# 13_IO_ETH.net
KiCad netlist of a schematic drawn in Altium Designer
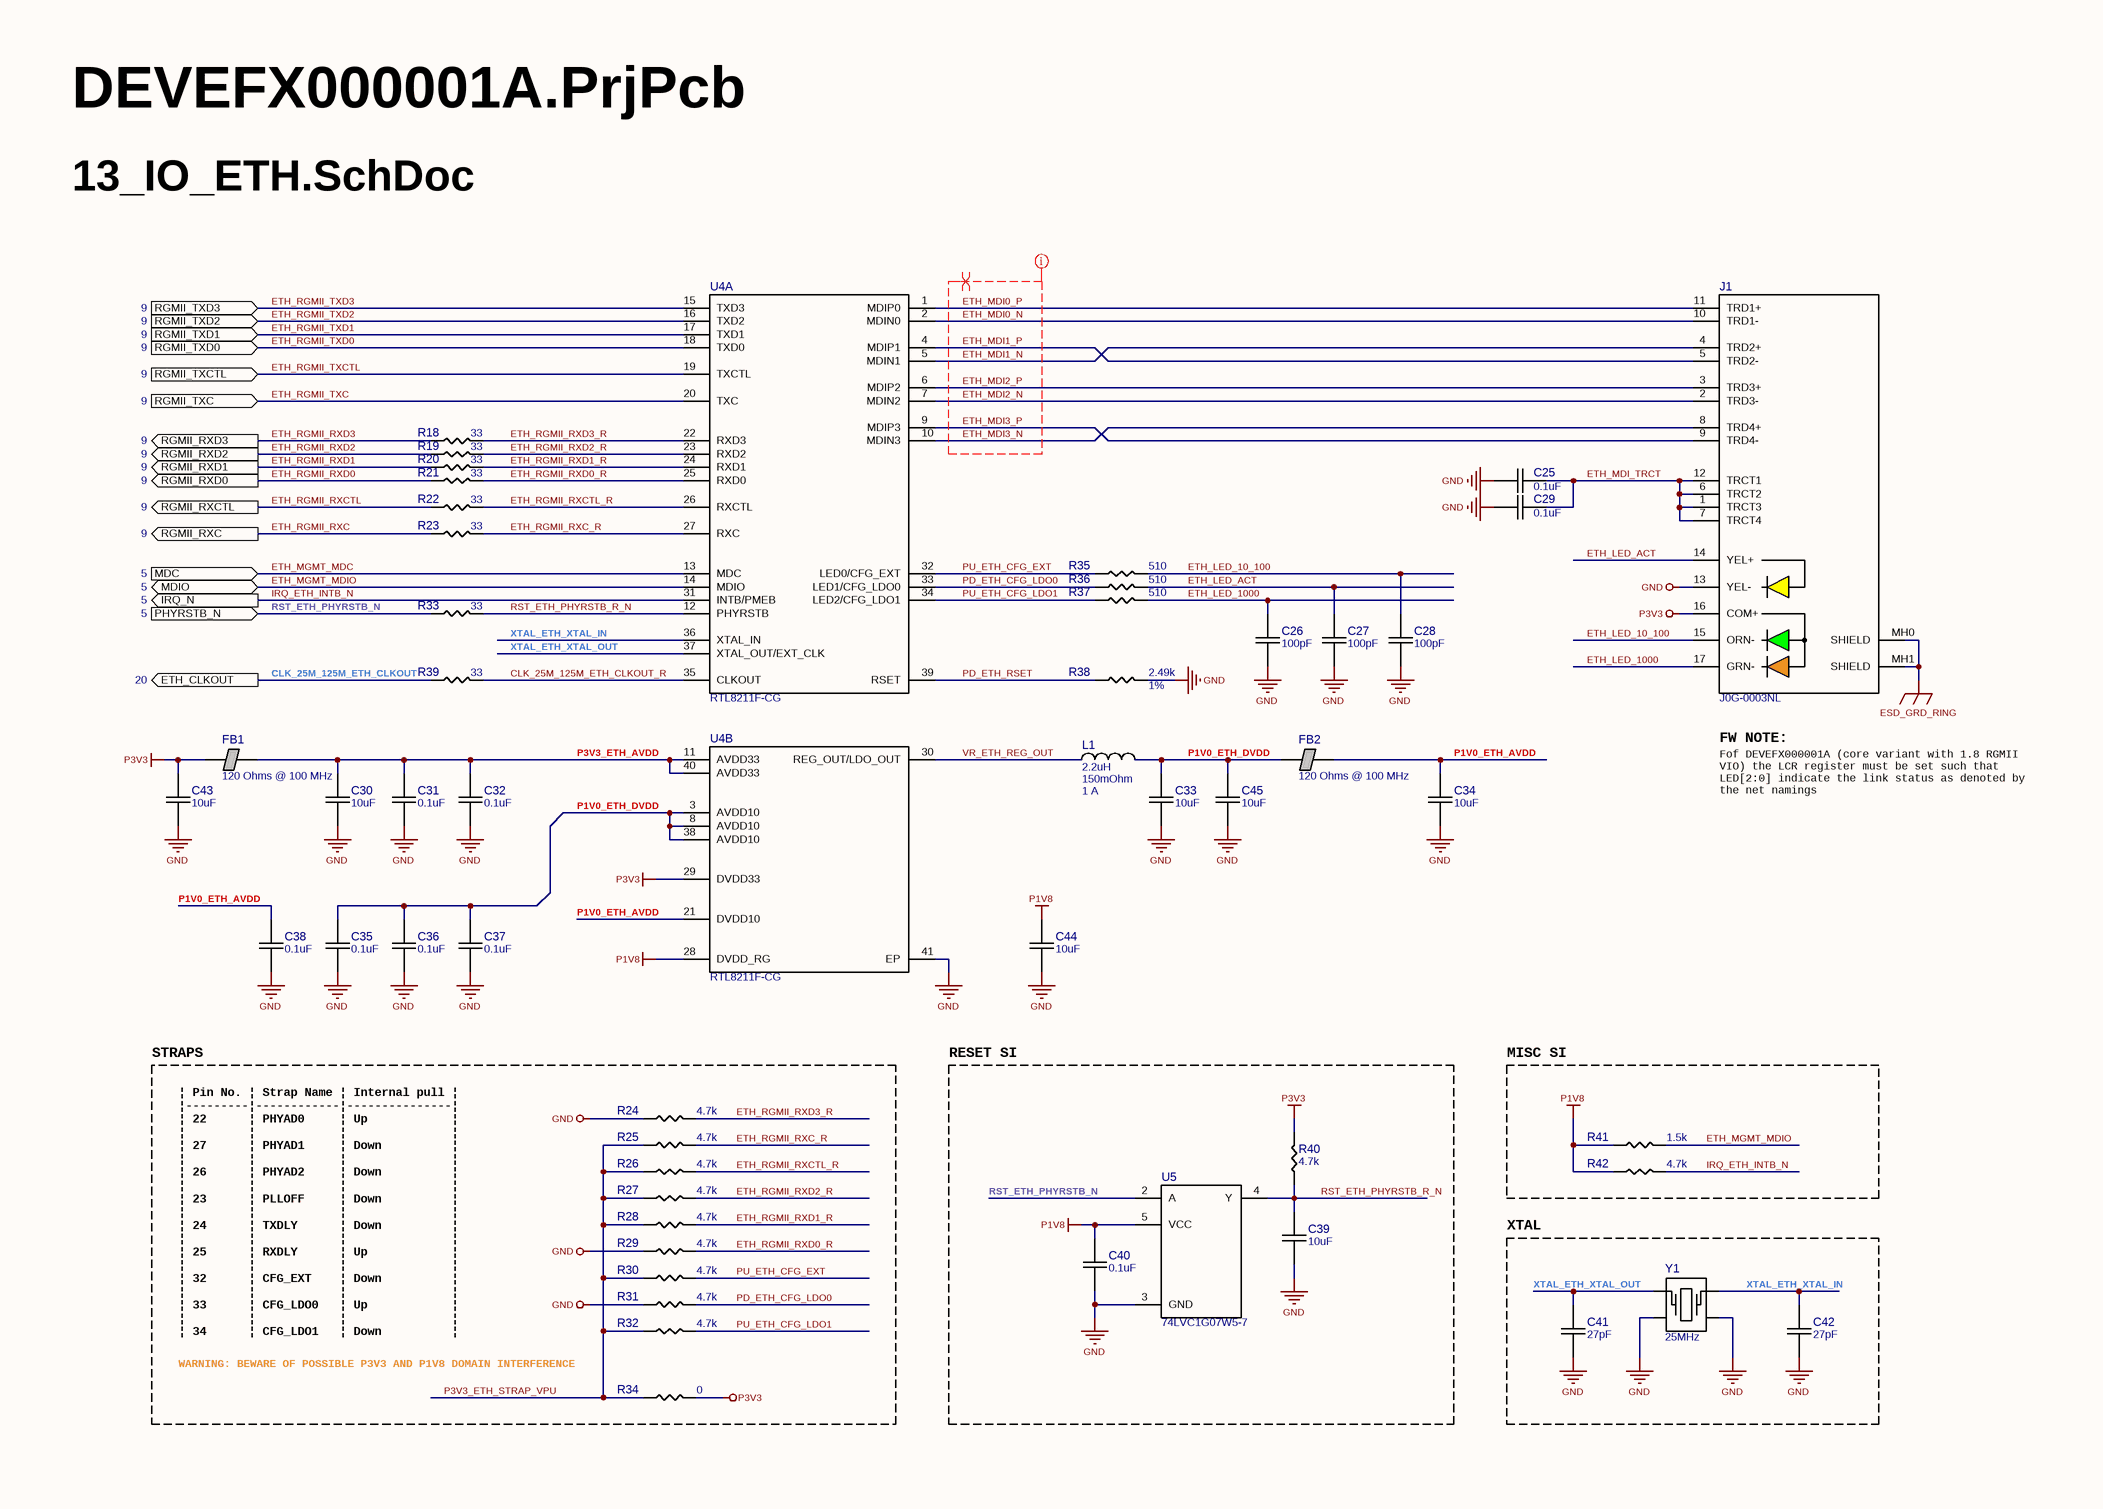
[diagram p0: 13_IO_ETH.SchDoc]

(export (version "E")
  (design (tool "Eeschema 10.0.6"))
  (components
    (comp (ref "C25")
      (value "0.1uF")
      (footprint "CAPC1005X06N")
      (description "CAP CER 0.1UF 25V X7R 0402")
      (fields (field (name "PART NUMBER") "GRM155R71E104KE14J") (field (name "VOLTAGE") "25V"))
      (libsource (lib "Database") (part "Capacitor"))
    )
    (comp (ref "C26")
      (value "100pF")
      (footprint "CAPC1005X06N")
      (description "CAP CER 100PF 50V C0G/NP0 0402")
      (fields (field (name "PART NUMBER") "GCM1555C1H101FA16J") (field (name "VOLTAGE") "50V"))
      (libsource (lib "Database") (part "Capacitor"))
    )
    (comp (ref "C27")
      (value "100pF")
      (footprint "CAPC1005X06N")
      (description "CAP CER 100PF 50V C0G/NP0 0402")
      (fields (field (name "PART NUMBER") "GCM1555C1H101FA16J") (field (name "VOLTAGE") "50V"))
      (libsource (lib "Database") (part "Capacitor"))
    )
    (comp (ref "C28")
      (value "100pF")
      (footprint "CAPC1005X06N")
      (description "CAP CER 100PF 50V C0G/NP0 0402")
      (fields (field (name "PART NUMBER") "GCM1555C1H101FA16J") (field (name "VOLTAGE") "50V"))
      (libsource (lib "Database") (part "Capacitor"))
    )
    (comp (ref "C29")
      (value "0.1uF")
      (footprint "CAPC1005X06N")
      (description "CAP CER 0.1UF 25V X7R 0402")
      (fields (field (name "PART NUMBER") "GRM155R71E104KE14J") (field (name "VOLTAGE") "25V"))
      (libsource (lib "Database") (part "Capacitor"))
    )
    (comp (ref "C30")
      (value "10uF")
      (footprint "CAPC1005X06N")
      (description "CAP CER 10UF 6.3V X5R 0402")
      (fields (field (name "PART NUMBER") "GRM155R60J106ME47D") (field (name "VOLTAGE") "6.3V"))
      (libsource (lib "Database") (part "Capacitor"))
    )
    (comp (ref "C31")
      (value "0.1uF")
      (footprint "CAPC1005X06N")
      (description "CAP CER 0.1UF 25V X7R 0402")
      (fields (field (name "PART NUMBER") "GRM155R71E104KE14J") (field (name "VOLTAGE") "25V"))
      (libsource (lib "Database") (part "Capacitor"))
    )
    (comp (ref "C32")
      (value "0.1uF")
      (footprint "CAPC1005X06N")
      (description "CAP CER 0.1UF 25V X7R 0402")
      (fields (field (name "PART NUMBER") "GRM155R71E104KE14J") (field (name "VOLTAGE") "25V"))
      (libsource (lib "Database") (part "Capacitor"))
    )
    (comp (ref "C33")
      (value "10uF")
      (footprint "CAPC1005X06N")
      (description "CAP CER 10UF 6.3V X5R 0402")
      (fields (field (name "PART NUMBER") "GRM155R60J106ME47D") (field (name "VOLTAGE") "6.3V"))
      (libsource (lib "Database") (part "Capacitor"))
    )
    (comp (ref "C34")
      (value "10uF")
      (footprint "CAPC1005X06N")
      (description "CAP CER 10UF 6.3V X5R 0402")
      (fields (field (name "PART NUMBER") "GRM155R60J106ME47D") (field (name "VOLTAGE") "6.3V"))
      (libsource (lib "Database") (part "Capacitor"))
    )
    (comp (ref "C35")
      (value "0.1uF")
      (footprint "CAPC1005X06N")
      (description "CAP CER 0.1UF 25V X7R 0402")
      (fields (field (name "PART NUMBER") "GRM155R71E104KE14J") (field (name "VOLTAGE") "25V"))
      (libsource (lib "Database") (part "Capacitor"))
    )
    (comp (ref "C36")
      (value "0.1uF")
      (footprint "CAPC1005X06N")
      (description "CAP CER 0.1UF 25V X7R 0402")
      (fields (field (name "PART NUMBER") "GRM155R71E104KE14J") (field (name "VOLTAGE") "25V"))
      (libsource (lib "Database") (part "Capacitor"))
    )
    (comp (ref "C37")
      (value "0.1uF")
      (footprint "CAPC1005X06N")
      (description "CAP CER 0.1UF 25V X7R 0402")
      (fields (field (name "PART NUMBER") "GRM155R71E104KE14J") (field (name "VOLTAGE") "25V"))
      (libsource (lib "Database") (part "Capacitor"))
    )
    (comp (ref "C38")
      (value "0.1uF")
      (footprint "CAPC1005X06N")
      (description "CAP CER 0.1UF 25V X7R 0402")
      (fields (field (name "PART NUMBER") "GRM155R71E104KE14J") (field (name "VOLTAGE") "25V"))
      (libsource (lib "Database") (part "Capacitor"))
    )
    (comp (ref "C39")
      (value "10uF")
      (footprint "CAPC1005X06N")
      (description "CAP CER 10UF 6.3V X5R 0402")
      (fields (field (name "PART NUMBER") "GRM155R60J106ME47D") (field (name "VOLTAGE") "6.3V"))
      (libsource (lib "Database") (part "Capacitor"))
    )
    (comp (ref "C40")
      (value "0.1uF")
      (footprint "CAPC1005X06N")
      (description "CAP CER 0.1UF 25V X7R 0402")
      (fields (field (name "PART NUMBER") "GRM155R71E104KE14J") (field (name "VOLTAGE") "25V"))
      (libsource (lib "Database") (part "Capacitor"))
    )
    (comp (ref "C41")
      (value "27pF")
      (footprint "CAPC1005X06N")
      (description "CAP CER 27PF 50V C0G/NPO 0402")
      (fields (field (name "PART NUMBER") "CC0402JRNPO9BN270") (field (name "VOLTAGE") "50V"))
      (libsource (lib "Database") (part "Capacitor"))
    )
    (comp (ref "C42")
      (value "27pF")
      (footprint "CAPC1005X06N")
      (description "CAP CER 27PF 50V C0G/NPO 0402")
      (fields (field (name "PART NUMBER") "CC0402JRNPO9BN270") (field (name "VOLTAGE") "50V"))
      (libsource (lib "Database") (part "Capacitor"))
    )
    (comp (ref "C43")
      (value "10uF")
      (footprint "CAPC1005X06N")
      (description "CAP CER 10UF 6.3V X5R 0402")
      (fields (field (name "PART NUMBER") "GRM155R60J106ME47D") (field (name "VOLTAGE") "6.3V"))
      (libsource (lib "Database") (part "Capacitor"))
    )
    (comp (ref "C44")
      (value "10uF")
      (footprint "CAPC1005X06N")
      (description "CAP CER 10UF 6.3V X5R 0402")
      (fields (field (name "PART NUMBER") "GRM155R60J106ME47D") (field (name "VOLTAGE") "6.3V"))
      (libsource (lib "Database") (part "Capacitor"))
    )
    (comp (ref "C45")
      (value "10uF")
      (footprint "CAPC1005X06N")
      (description "CAP CER 10UF 6.3V X5R 0402")
      (fields (field (name "PART NUMBER") "GRM155R60J106ME47D") (field (name "VOLTAGE") "6.3V"))
      (libsource (lib "Database") (part "Capacitor"))
    )
    (comp (ref "FB1")
      (value "120 Ohms @ 100 MHz")
      (footprint "INDC1005X05N")
      (description "FERRITE BEAD 120 OHM 0402 1LN")
      (fields (field (name "PART NUMBER") "BLM15PD121SN1D"))
      (libsource (lib "Database") (part "Bead"))
    )
    (comp (ref "FB2")
      (value "120 Ohms @ 100 MHz")
      (footprint "INDC1005X05N")
      (description "FERRITE BEAD 120 OHM 0402 1LN")
      (fields (field (name "PART NUMBER") "BLM15PD121SN1D"))
      (libsource (lib "Database") (part "Bead"))
    )
    (comp (ref "J1")
      (value "J0G-0003NL")
      (footprint "PULSE_J0G-0003NL")
      (description "CONN JACK 1PORT 1000 BASE-T PCB")
      (libsource (lib "Database") (part "J0G-0003NL"))
    )
    (comp (ref "L1")
      (value "2.2uH")
      (footprint "INDC2520X12N")
      (description "FIXED IND 2.2UH 1A 150 MOHM SMD")
      (fields
        (field (name "PART NUMBER") "LQM2HPN2R2MJ0L")
        (field (name "DCR") "150mOhm")
        (field (name "IR") "1 A")
      )
      (libsource (lib "Database") (part "Inductor"))
    )
    (comp (ref "R18")
      (value "33")
      (footprint "RESC1005X03N")
      (description "RES SMD 33 OHM 1% 1/16W 0402")
      (fields (field (name "PART NUMBER") "RC0402FR-0733RL"))
      (libsource (lib "Database") (part "Resistor_ENG"))
    )
    (comp (ref "R19")
      (value "33")
      (footprint "RESC1005X03N")
      (description "RES SMD 33 OHM 1% 1/16W 0402")
      (fields (field (name "PART NUMBER") "RC0402FR-0733RL"))
      (libsource (lib "Database") (part "Resistor_ENG"))
    )
    (comp (ref "R20")
      (value "33")
      (footprint "RESC1005X03N")
      (description "RES SMD 33 OHM 1% 1/16W 0402")
      (fields (field (name "PART NUMBER") "RC0402FR-0733RL"))
      (libsource (lib "Database") (part "Resistor_ENG"))
    )
    (comp (ref "R21")
      (value "33")
      (footprint "RESC1005X03N")
      (description "RES SMD 33 OHM 1% 1/16W 0402")
      (fields (field (name "PART NUMBER") "RC0402FR-0733RL"))
      (libsource (lib "Database") (part "Resistor_ENG"))
    )
    (comp (ref "R22")
      (value "33")
      (footprint "RESC1005X03N")
      (description "RES SMD 33 OHM 1% 1/16W 0402")
      (fields (field (name "PART NUMBER") "RC0402FR-0733RL"))
      (libsource (lib "Database") (part "Resistor_ENG"))
    )
    (comp (ref "R23")
      (value "33")
      (footprint "RESC1005X03N")
      (description "RES SMD 33 OHM 1% 1/16W 0402")
      (fields (field (name "PART NUMBER") "RC0402FR-0733RL"))
      (libsource (lib "Database") (part "Resistor_ENG"))
    )
    (comp (ref "R24")
      (value "4.7k")
      (footprint "RESC1005X03N")
      (description "RES SMD 4.7K OHM 1% 1/16W 0402")
      (fields (field (name "PART NUMBER") "RC0402FR-074K7L"))
      (libsource (lib "Database") (part "Resistor_ENG"))
    )
    (comp (ref "R25")
      (value "4.7k")
      (footprint "RESC1005X03N")
      (description "RES SMD 4.7K OHM 1% 1/16W 0402")
      (fields (field (name "PART NUMBER") "RC0402FR-074K7L"))
      (libsource (lib "Database") (part "Resistor_ENG"))
    )
    (comp (ref "R26")
      (value "4.7k")
      (footprint "RESC1005X03N")
      (description "RES SMD 4.7K OHM 1% 1/16W 0402")
      (fields (field (name "PART NUMBER") "RC0402FR-074K7L"))
      (libsource (lib "Database") (part "Resistor_ENG"))
    )
    (comp (ref "R27")
      (value "4.7k")
      (footprint "RESC1005X03N")
      (description "RES SMD 4.7K OHM 1% 1/16W 0402")
      (fields (field (name "PART NUMBER") "RC0402FR-074K7L"))
      (libsource (lib "Database") (part "Resistor_ENG"))
    )
    (comp (ref "R28")
      (value "4.7k")
      (footprint "RESC1005X03N")
      (description "RES SMD 4.7K OHM 1% 1/16W 0402")
      (fields (field (name "PART NUMBER") "RC0402FR-074K7L"))
      (libsource (lib "Database") (part "Resistor_ENG"))
    )
    (comp (ref "R29")
      (value "4.7k")
      (footprint "RESC1005X03N")
      (description "RES SMD 4.7K OHM 1% 1/16W 0402")
      (fields (field (name "PART NUMBER") "RC0402FR-074K7L"))
      (libsource (lib "Database") (part "Resistor_ENG"))
    )
    (comp (ref "R30")
      (value "4.7k")
      (footprint "RESC1005X03N")
      (description "RES SMD 4.7K OHM 1% 1/16W 0402")
      (fields (field (name "PART NUMBER") "RC0402FR-074K7L"))
      (libsource (lib "Database") (part "Resistor_ENG"))
    )
    (comp (ref "R31")
      (value "4.7k")
      (footprint "RESC1005X03N")
      (description "RES SMD 4.7K OHM 1% 1/16W 0402")
      (fields (field (name "PART NUMBER") "RC0402FR-074K7L"))
      (libsource (lib "Database") (part "Resistor_ENG"))
    )
    (comp (ref "R32")
      (value "4.7k")
      (footprint "RESC1005X03N")
      (description "RES SMD 4.7K OHM 1% 1/16W 0402")
      (fields (field (name "PART NUMBER") "RC0402FR-074K7L"))
      (libsource (lib "Database") (part "Resistor_ENG"))
    )
    (comp (ref "R33")
      (value "33")
      (footprint "RESC1005X03N")
      (description "RES SMD 33 OHM 1% 1/16W 0402")
      (fields (field (name "PART NUMBER") "RC0402FR-0733RL"))
      (libsource (lib "Database") (part "Resistor_ENG"))
    )
    (comp (ref "R34")
      (value "0")
      (footprint "RESC1005X03N")
      (description "RES SMD 0 OHM JUMPER 1/16W 0402")
      (fields (field (name "PART NUMBER") "RC0402FR-070RL"))
      (libsource (lib "Database") (part "Resistor_ENG"))
    )
    (comp (ref "R35")
      (value "510")
      (footprint "RESC1005X03N")
      (description "RES 510 OHM 5% 1/16W 0402")
      (fields (field (name "PART NUMBER") "RC0402JR-07510RL"))
      (libsource (lib "Database") (part "Resistor_ENG"))
    )
    (comp (ref "R36")
      (value "510")
      (footprint "RESC1005X03N")
      (description "RES 510 OHM 5% 1/16W 0402")
      (fields (field (name "PART NUMBER") "RC0402JR-07510RL"))
      (libsource (lib "Database") (part "Resistor_ENG"))
    )
    (comp (ref "R37")
      (value "510")
      (footprint "RESC1005X03N")
      (description "RES 510 OHM 5% 1/16W 0402")
      (fields (field (name "PART NUMBER") "RC0402JR-07510RL"))
      (libsource (lib "Database") (part "Resistor_ENG"))
    )
    (comp (ref "R38")
      (value "2.49k")
      (footprint "RESC1005X03N")
      (description "RES SMD 2.49K OHM 1% 1/16W 0402")
      (fields (field (name "PART NUMBER") "RC0402FR-072K49L") (field (name "TOL") "1%"))
      (libsource (lib "Database") (part "Resistor_ENG"))
    )
    (comp (ref "R39")
      (value "33")
      (footprint "RESC1005X03N")
      (description "RES SMD 33 OHM 1% 1/16W 0402")
      (fields (field (name "PART NUMBER") "RC0402FR-0733RL"))
      (libsource (lib "Database") (part "Resistor_ENG"))
    )
    (comp (ref "R40")
      (value "4.7k")
      (footprint "RESC1005X03N")
      (description "RES SMD 4.7K OHM 1% 1/16W 0402")
      (fields (field (name "PART NUMBER") "RC0402FR-074K7L"))
      (libsource (lib "Database") (part "Resistor_ENG"))
    )
    (comp (ref "R41")
      (value "1.5k")
      (footprint "RESC1005X03N")
      (description "RES 1.5K OHM 1% 1/16W 0402")
      (fields (field (name "PART NUMBER") "RC0402FR-071K5L"))
      (libsource (lib "Database") (part "Resistor_ENG"))
    )
    (comp (ref "R42")
      (value "4.7k")
      (footprint "RESC1005X03N")
      (description "RES SMD 4.7K OHM 1% 1/16W 0402")
      (fields (field (name "PART NUMBER") "RC0402FR-074K7L"))
      (libsource (lib "Database") (part "Resistor_ENG"))
    )
    (comp (ref "U4")
      (value "RTL8211F-CG")
      (footprint "QFN40P500X500X90_HS-41N")
      (description "Phy 1-CH 10MBPS/100MBPS/1GBPS 3.3V 40-PIN QFN Ep")
      (libsource (lib "Database") (part "RTL8211F"))
    )
    (comp (ref "U5")
      (value "74LVC1G07W5-7")
      (footprint "SOT95P280X145-5N")
      (description "IC BUFFER NON-INVERT 5.5V SOT25")
      (libsource (lib "Database") (part "74LVC1G07_SOT"))
    )
    (comp (ref "Y1")
      (value "25MHz")
      (footprint "XTAL_3225")
      (description "CRYSTAL 25.0000MHZ 18PF SMD")
      (fields (field (name "PART NUMBER") "TSX-3225 25.0000MF10P-C0"))
      (libsource (lib "Database") (part "Crystal_1"))
    )
  )
  (nets
    (net (code "1") (name "/CLK_25M_125M_ETH_CLKOUT") (class "Default")
      (node (ref "R39") (pin "1") (pinfunction "1_1") (pintype "passive"))
    )
    (net (code "2") (name "/CLK_25M_125M_ETH_CLKOUT_R") (class "Default")
      (node (ref "R39") (pin "2") (pinfunction "2_2") (pintype "passive"))
      (node (ref "U4") (pin "35") (pinfunction "CLKOUT_35") (pintype "passive"))
    )
    (net (code "3") (name "/ETH_LED_10_100") (class "Default")
      (node (ref "C28") (pin "2") (pinfunction "2_2") (pintype "passive"))
      (node (ref "J1") (pin "15") (pinfunction "ORN-_15") (pintype "passive"))
      (node (ref "R35") (pin "2") (pinfunction "2_2") (pintype "passive"))
    )
    (net (code "4") (name "/ETH_LED_1000") (class "Default")
      (node (ref "C26") (pin "2") (pinfunction "2_2") (pintype "passive"))
      (node (ref "J1") (pin "17") (pinfunction "GRN-_17") (pintype "passive"))
      (node (ref "R37") (pin "2") (pinfunction "2_2") (pintype "passive"))
    )
    (net (code "5") (name "/ETH_LED_ACT") (class "Default")
      (node (ref "C27") (pin "2") (pinfunction "2_2") (pintype "passive"))
      (node (ref "J1") (pin "14") (pinfunction "YEL+_14") (pintype "passive"))
      (node (ref "R36") (pin "2") (pinfunction "2_2") (pintype "passive"))
    )
    (net (code "6") (name "/ETH_MDI0_N") (class "Default")
      (node (ref "J1") (pin "10") (pinfunction "TRD1-_10") (pintype "passive"))
      (node (ref "U4") (pin "2") (pinfunction "MDIN0_2") (pintype "passive"))
    )
    (net (code "7") (name "/ETH_MDI0_P") (class "Default")
      (node (ref "J1") (pin "11") (pinfunction "TRD1+_11") (pintype "passive"))
      (node (ref "U4") (pin "1") (pinfunction "MDIP0_1") (pintype "passive"))
    )
    (net (code "8") (name "/ETH_MDI1_N") (class "Default")
      (node (ref "J1") (pin "4") (pinfunction "TRD2+_4") (pintype "passive"))
      (node (ref "U4") (pin "5") (pinfunction "MDIN1_5") (pintype "passive"))
    )
    (net (code "9") (name "/ETH_MDI1_P") (class "Default")
      (node (ref "J1") (pin "5") (pinfunction "TRD2-_5") (pintype "passive"))
      (node (ref "U4") (pin "4") (pinfunction "MDIP1_4") (pintype "passive"))
    )
    (net (code "10") (name "/ETH_MDI2_N") (class "Default")
      (node (ref "J1") (pin "2") (pinfunction "TRD3-_2") (pintype "passive"))
      (node (ref "U4") (pin "7") (pinfunction "MDIN2_7") (pintype "passive"))
    )
    (net (code "11") (name "/ETH_MDI2_P") (class "Default")
      (node (ref "J1") (pin "3") (pinfunction "TRD3+_3") (pintype "passive"))
      (node (ref "U4") (pin "6") (pinfunction "MDIP2_6") (pintype "passive"))
    )
    (net (code "12") (name "/ETH_MDI3_N") (class "Default")
      (node (ref "J1") (pin "8") (pinfunction "TRD4+_8") (pintype "passive"))
      (node (ref "U4") (pin "10") (pinfunction "MDIN3_10") (pintype "passive"))
    )
    (net (code "13") (name "/ETH_MDI3_P") (class "Default")
      (node (ref "J1") (pin "9") (pinfunction "TRD4-_9") (pintype "passive"))
      (node (ref "U4") (pin "9") (pinfunction "MDIP3_9") (pintype "passive"))
    )
    (net (code "14") (name "/ETH_MDI_TRCT") (class "Default")
      (node (ref "C25") (pin "2") (pinfunction "2_2") (pintype "passive"))
      (node (ref "C29") (pin "2") (pinfunction "2_2") (pintype "passive"))
      (node (ref "J1") (pin "1") (pinfunction "TRCT3_1") (pintype "passive"))
      (node (ref "J1") (pin "12") (pinfunction "TRCT1_12") (pintype "passive"))
      (node (ref "J1") (pin "6") (pinfunction "TRCT2_6") (pintype "passive"))
      (node (ref "J1") (pin "7") (pinfunction "TRCT4_7") (pintype "passive"))
    )
    (net (code "15") (name "/ETH_MGMT_MDC") (class "Default")
      (node (ref "U4") (pin "13") (pinfunction "MDC_13") (pintype "passive"))
    )
    (net (code "16") (name "/ETH_MGMT_MDIO") (class "Default")
      (node (ref "R41") (pin "2") (pinfunction "2_2") (pintype "passive"))
      (node (ref "U4") (pin "14") (pinfunction "MDIO_14") (pintype "passive"))
    )
    (net (code "17") (name "/ETH_RGMII_RXC") (class "Default")
      (node (ref "R23") (pin "1") (pinfunction "1_1") (pintype "passive"))
    )
    (net (code "18") (name "/ETH_RGMII_RXCTL") (class "Default")
      (node (ref "R22") (pin "1") (pinfunction "1_1") (pintype "passive"))
    )
    (net (code "19") (name "/ETH_RGMII_RXCTL_R") (class "Default")
      (node (ref "R22") (pin "2") (pinfunction "2_2") (pintype "passive"))
      (node (ref "R26") (pin "2") (pinfunction "2_2") (pintype "passive"))
      (node (ref "U4") (pin "26") (pinfunction "RXCTL_26") (pintype "passive"))
    )
    (net (code "20") (name "/ETH_RGMII_RXC_R") (class "Default")
      (node (ref "R23") (pin "2") (pinfunction "2_2") (pintype "passive"))
      (node (ref "R25") (pin "2") (pinfunction "2_2") (pintype "passive"))
      (node (ref "U4") (pin "27") (pinfunction "RXC_27") (pintype "passive"))
    )
    (net (code "21") (name "/ETH_RGMII_RXD0") (class "Default")
      (node (ref "R21") (pin "1") (pinfunction "1_1") (pintype "passive"))
    )
    (net (code "22") (name "/ETH_RGMII_RXD0_R") (class "Default")
      (node (ref "R21") (pin "2") (pinfunction "2_2") (pintype "passive"))
      (node (ref "R29") (pin "2") (pinfunction "2_2") (pintype "passive"))
      (node (ref "U4") (pin "25") (pinfunction "RXD0_25") (pintype "passive"))
    )
    (net (code "23") (name "/ETH_RGMII_RXD1") (class "Default")
      (node (ref "R20") (pin "1") (pinfunction "1_1") (pintype "passive"))
    )
    (net (code "24") (name "/ETH_RGMII_RXD1_R") (class "Default")
      (node (ref "R20") (pin "2") (pinfunction "2_2") (pintype "passive"))
      (node (ref "R28") (pin "2") (pinfunction "2_2") (pintype "passive"))
      (node (ref "U4") (pin "24") (pinfunction "RXD1_24") (pintype "passive"))
    )
    (net (code "25") (name "/ETH_RGMII_RXD2") (class "Default")
      (node (ref "R19") (pin "1") (pinfunction "1_1") (pintype "passive"))
    )
    (net (code "26") (name "/ETH_RGMII_RXD2_R") (class "Default")
      (node (ref "R19") (pin "2") (pinfunction "2_2") (pintype "passive"))
      (node (ref "R27") (pin "2") (pinfunction "2_2") (pintype "passive"))
      (node (ref "U4") (pin "23") (pinfunction "RXD2_23") (pintype "passive"))
    )
    (net (code "27") (name "/ETH_RGMII_RXD3") (class "Default")
      (node (ref "R18") (pin "1") (pinfunction "1_1") (pintype "passive"))
    )
    (net (code "28") (name "/ETH_RGMII_RXD3_R") (class "Default")
      (node (ref "R18") (pin "2") (pinfunction "2_2") (pintype "passive"))
      (node (ref "R24") (pin "2") (pinfunction "2_2") (pintype "passive"))
      (node (ref "U4") (pin "22") (pinfunction "RXD3_22") (pintype "passive"))
    )
    (net (code "29") (name "/ETH_RGMII_TXC") (class "Default")
      (node (ref "U4") (pin "20") (pinfunction "TXC_20") (pintype "passive"))
    )
    (net (code "30") (name "/ETH_RGMII_TXCTL") (class "Default")
      (node (ref "U4") (pin "19") (pinfunction "TXCTL_19") (pintype "passive"))
    )
    (net (code "31") (name "/ETH_RGMII_TXD0") (class "Default")
      (node (ref "U4") (pin "18") (pinfunction "TXD0_18") (pintype "passive"))
    )
    (net (code "32") (name "/ETH_RGMII_TXD1") (class "Default")
      (node (ref "U4") (pin "17") (pinfunction "TXD1_17") (pintype "passive"))
    )
    (net (code "33") (name "/ETH_RGMII_TXD2") (class "Default")
      (node (ref "U4") (pin "16") (pinfunction "TXD2_16") (pintype "passive"))
    )
    (net (code "34") (name "/ETH_RGMII_TXD3") (class "Default")
      (node (ref "U4") (pin "15") (pinfunction "TXD3_15") (pintype "passive"))
    )
    (net (code "35") (name "/IRQ_ETH_INTB_N") (class "Default")
      (node (ref "R42") (pin "2") (pinfunction "2_2") (pintype "passive"))
      (node (ref "U4") (pin "31") (pinfunction "INTB/PMEB_31") (pintype "passive"))
    )
    (net (code "36") (name "/P1V0_ETH_AVDD") (class "Default")
      (node (ref "C34") (pin "2") (pinfunction "2_2") (pintype "passive"))
      (node (ref "C38") (pin "2") (pinfunction "2_2") (pintype "passive"))
      (node (ref "FB2") (pin "2") (pinfunction "2_2") (pintype "passive"))
      (node (ref "U4") (pin "21") (pinfunction "DVDD10_21") (pintype "passive"))
    )
    (net (code "37") (name "/P1V0_ETH_DVDD") (class "Default")
      (node (ref "C33") (pin "2") (pinfunction "2_2") (pintype "passive"))
      (node (ref "C35") (pin "2") (pinfunction "2_2") (pintype "passive"))
      (node (ref "C36") (pin "2") (pinfunction "2_2") (pintype "passive"))
      (node (ref "C37") (pin "2") (pinfunction "2_2") (pintype "passive"))
      (node (ref "C45") (pin "2") (pinfunction "2_2") (pintype "passive"))
      (node (ref "FB2") (pin "1") (pinfunction "1_1") (pintype "passive"))
      (node (ref "L1") (pin "2") (pinfunction "2_2") (pintype "passive"))
      (node (ref "U4") (pin "3") (pinfunction "AVDD10_3") (pintype "passive"))
      (node (ref "U4") (pin "38") (pinfunction "AVDD10_38") (pintype "passive"))
      (node (ref "U4") (pin "8") (pinfunction "AVDD10_8") (pintype "passive"))
    )
    (net (code "38") (name "/P3V3_ETH_AVDD") (class "Default")
      (node (ref "C30") (pin "2") (pinfunction "2_2") (pintype "passive"))
      (node (ref "C31") (pin "2") (pinfunction "2_2") (pintype "passive"))
      (node (ref "C32") (pin "2") (pinfunction "2_2") (pintype "passive"))
      (node (ref "FB1") (pin "2") (pinfunction "2_2") (pintype "passive"))
      (node (ref "U4") (pin "11") (pinfunction "AVDD33_11") (pintype "passive"))
      (node (ref "U4") (pin "40") (pinfunction "AVDD33_40") (pintype "passive"))
    )
    (net (code "39") (name "/P3V3_ETH_STRAP_VPU") (class "Default")
      (node (ref "R25") (pin "1") (pinfunction "1_1") (pintype "passive"))
      (node (ref "R26") (pin "1") (pinfunction "1_1") (pintype "passive"))
      (node (ref "R27") (pin "1") (pinfunction "1_1") (pintype "passive"))
      (node (ref "R28") (pin "1") (pinfunction "1_1") (pintype "passive"))
      (node (ref "R30") (pin "1") (pinfunction "1_1") (pintype "passive"))
      (node (ref "R32") (pin "1") (pinfunction "1_1") (pintype "passive"))
      (node (ref "R34") (pin "1") (pinfunction "1_1") (pintype "passive"))
    )
    (net (code "40") (name "/PD_ETH_CFG_LDO0") (class "Default")
      (node (ref "R31") (pin "2") (pinfunction "2_2") (pintype "passive"))
      (node (ref "R36") (pin "1") (pinfunction "1_1") (pintype "passive"))
      (node (ref "U4") (pin "33") (pinfunction "LED1/CFG_LDO0_33") (pintype "passive"))
    )
    (net (code "41") (name "/PD_ETH_RSET") (class "Default")
      (node (ref "R38") (pin "1") (pinfunction "1_1") (pintype "passive"))
      (node (ref "U4") (pin "39") (pinfunction "RSET_39") (pintype "passive"))
    )
    (net (code "42") (name "/PU_ETH_CFG_EXT") (class "Default")
      (node (ref "R30") (pin "2") (pinfunction "2_2") (pintype "passive"))
      (node (ref "R35") (pin "1") (pinfunction "1_1") (pintype "passive"))
      (node (ref "U4") (pin "32") (pinfunction "LED0/CFG_EXT_32") (pintype "passive"))
    )
    (net (code "43") (name "/PU_ETH_CFG_LDO1") (class "Default")
      (node (ref "R32") (pin "2") (pinfunction "2_2") (pintype "passive"))
      (node (ref "R37") (pin "1") (pinfunction "1_1") (pintype "passive"))
      (node (ref "U4") (pin "34") (pinfunction "LED2/CFG_LDO1_34") (pintype "passive"))
    )
    (net (code "44") (name "/RST_ETH_PHYRSTB_N") (class "Default")
      (node (ref "R33") (pin "1") (pinfunction "1_1") (pintype "passive"))
      (node (ref "U5") (pin "2") (pinfunction "A_2") (pintype "passive"))
    )
    (net (code "45") (name "/RST_ETH_PHYRSTB_R_N") (class "Default")
      (node (ref "C39") (pin "2") (pinfunction "2_2") (pintype "passive"))
      (node (ref "R33") (pin "2") (pinfunction "2_2") (pintype "passive"))
      (node (ref "R40") (pin "1") (pinfunction "1_1") (pintype "passive"))
      (node (ref "U4") (pin "12") (pinfunction "PHYRSTB_12") (pintype "passive"))
      (node (ref "U5") (pin "4") (pinfunction "Y_4") (pintype "passive"))
    )
    (net (code "46") (name "/VR_ETH_REG_OUT") (class "Default")
      (node (ref "L1") (pin "1") (pinfunction "1_1") (pintype "passive"))
      (node (ref "U4") (pin "30") (pinfunction "REG_OUT/LDO_OUT_30") (pintype "passive"))
    )
    (net (code "47") (name "/XTAL_ETH_XTAL_IN") (class "Default")
      (node (ref "C42") (pin "2") (pinfunction "2_2") (pintype "passive"))
      (node (ref "U4") (pin "36") (pinfunction "XTAL_IN_36") (pintype "passive"))
      (node (ref "Y1") (pin "3") (pinfunction "3_3") (pintype "passive"))
    )
    (net (code "48") (name "/XTAL_ETH_XTAL_OUT") (class "Default")
      (node (ref "C41") (pin "2") (pinfunction "2_2") (pintype "passive"))
      (node (ref "U4") (pin "37") (pinfunction "XTAL_OUT/EXT_CLK_37") (pintype "passive"))
      (node (ref "Y1") (pin "1") (pinfunction "1_1") (pintype "passive"))
    )
    (net (code "49") (name "ESD_GRD_RING") (class "Default")
      (node (ref "J1") (pin "MH0") (pinfunction "SHIELD_MH0") (pintype "passive"))
      (node (ref "J1") (pin "MH1") (pinfunction "SHIELD_MH1") (pintype "passive"))
    )
    (net (code "50") (name "GND") (class "Default")
      (node (ref "C25") (pin "1") (pinfunction "1_1") (pintype "passive"))
      (node (ref "C26") (pin "1") (pinfunction "1_1") (pintype "passive"))
      (node (ref "C27") (pin "1") (pinfunction "1_1") (pintype "passive"))
      (node (ref "C28") (pin "1") (pinfunction "1_1") (pintype "passive"))
      (node (ref "C29") (pin "1") (pinfunction "1_1") (pintype "passive"))
      (node (ref "C30") (pin "1") (pinfunction "1_1") (pintype "passive"))
      (node (ref "C31") (pin "1") (pinfunction "1_1") (pintype "passive"))
      (node (ref "C32") (pin "1") (pinfunction "1_1") (pintype "passive"))
      (node (ref "C33") (pin "1") (pinfunction "1_1") (pintype "passive"))
      (node (ref "C34") (pin "1") (pinfunction "1_1") (pintype "passive"))
      (node (ref "C35") (pin "1") (pinfunction "1_1") (pintype "passive"))
      (node (ref "C36") (pin "1") (pinfunction "1_1") (pintype "passive"))
      (node (ref "C37") (pin "1") (pinfunction "1_1") (pintype "passive"))
      (node (ref "C38") (pin "1") (pinfunction "1_1") (pintype "passive"))
      (node (ref "C39") (pin "1") (pinfunction "1_1") (pintype "passive"))
      (node (ref "C40") (pin "1") (pinfunction "1_1") (pintype "passive"))
      (node (ref "C41") (pin "1") (pinfunction "1_1") (pintype "passive"))
      (node (ref "C42") (pin "1") (pinfunction "1_1") (pintype "passive"))
      (node (ref "C43") (pin "1") (pinfunction "1_1") (pintype "passive"))
      (node (ref "C44") (pin "1") (pinfunction "1_1") (pintype "passive"))
      (node (ref "C45") (pin "1") (pinfunction "1_1") (pintype "passive"))
      (node (ref "J1") (pin "13") (pinfunction "YEL-_13") (pintype "passive"))
      (node (ref "R24") (pin "1") (pinfunction "1_1") (pintype "passive"))
      (node (ref "R29") (pin "1") (pinfunction "1_1") (pintype "passive"))
      (node (ref "R31") (pin "1") (pinfunction "1_1") (pintype "passive"))
      (node (ref "R38") (pin "2") (pinfunction "2_2") (pintype "passive"))
      (node (ref "U4") (pin "41") (pinfunction "EP_41") (pintype "passive"))
      (node (ref "U5") (pin "3") (pinfunction "GND_3") (pintype "passive"))
      (node (ref "Y1") (pin "2") (pinfunction "2_2") (pintype "passive"))
      (node (ref "Y1") (pin "4") (pinfunction "4_4") (pintype "passive"))
    )
    (net (code "51") (name "P1V8") (class "Default")
      (node (ref "C40") (pin "2") (pinfunction "2_2") (pintype "passive"))
      (node (ref "C44") (pin "2") (pinfunction "2_2") (pintype "passive"))
      (node (ref "R41") (pin "1") (pinfunction "1_1") (pintype "passive"))
      (node (ref "R42") (pin "1") (pinfunction "1_1") (pintype "passive"))
      (node (ref "U4") (pin "28") (pinfunction "DVDD_RG_28") (pintype "passive"))
      (node (ref "U5") (pin "5") (pinfunction "VCC_5") (pintype "passive"))
    )
    (net (code "52") (name "P3V3") (class "Default")
      (node (ref "C43") (pin "2") (pinfunction "2_2") (pintype "passive"))
      (node (ref "FB1") (pin "1") (pinfunction "1_1") (pintype "passive"))
      (node (ref "J1") (pin "16") (pinfunction "COM+_16") (pintype "passive"))
      (node (ref "R34") (pin "2") (pinfunction "2_2") (pintype "passive"))
      (node (ref "R40") (pin "2") (pinfunction "2_2") (pintype "passive"))
      (node (ref "U4") (pin "29") (pinfunction "DVDD33_29") (pintype "passive"))
    )
  )
)
